# 5_power.net
KiCad netlist of a schematic drawn in Altium Designer
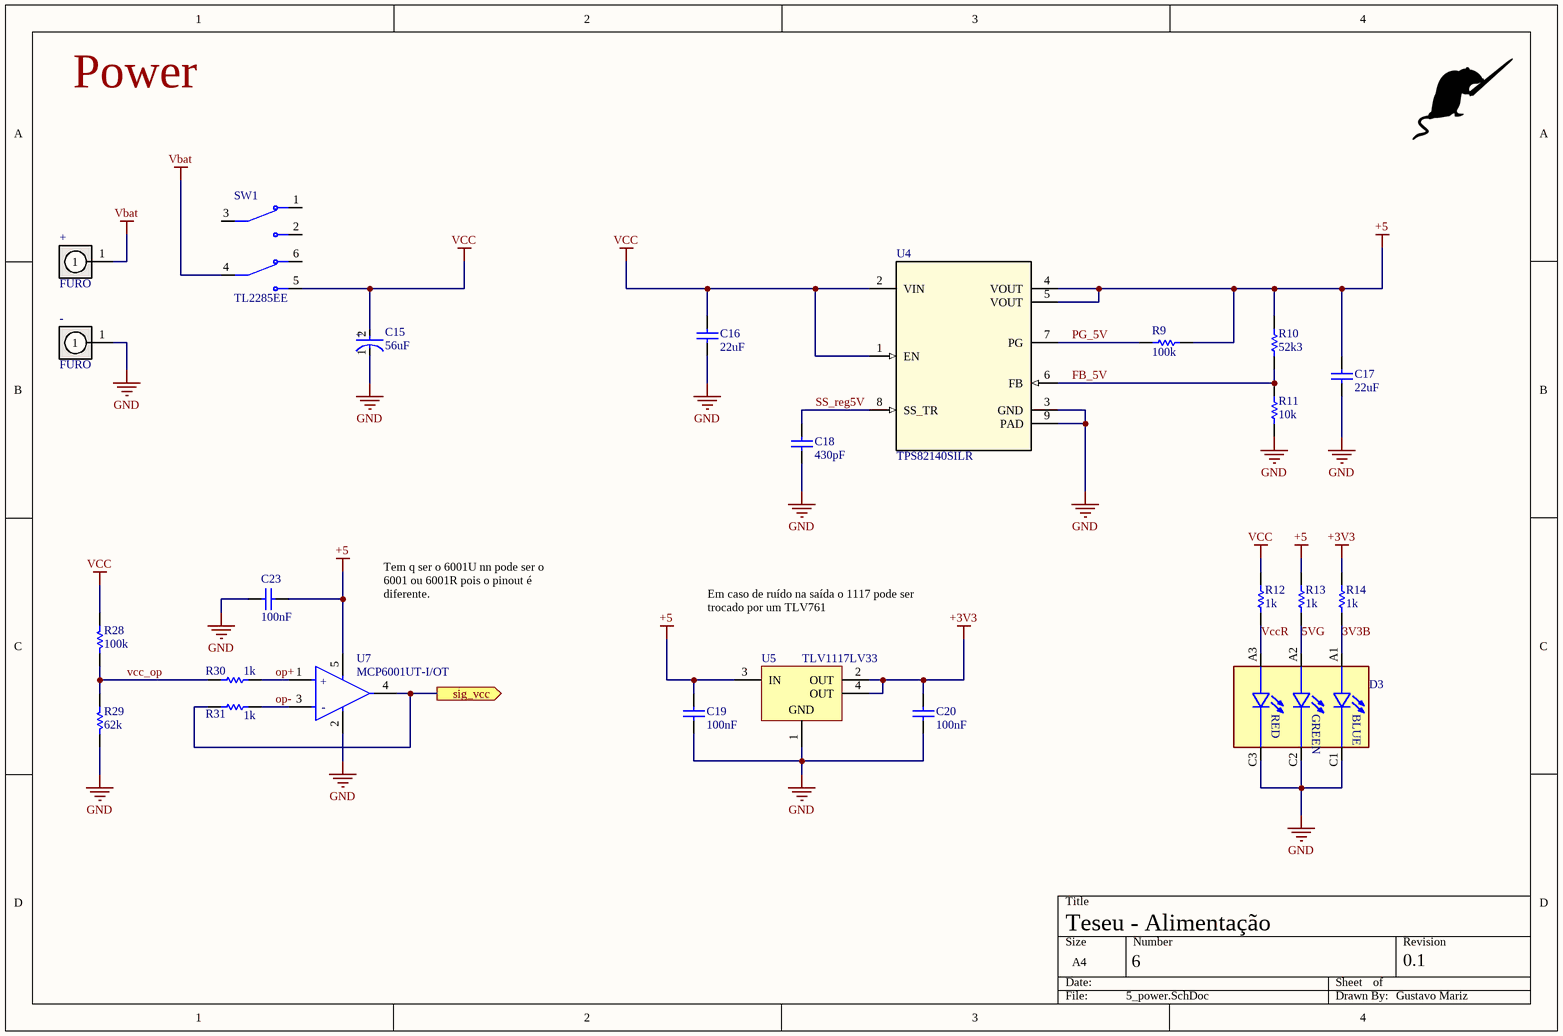
[diagram p0: 5_power.SchDoc]

(export (version "E")
  (design (tool "Eeschema 10.0.6"))
  (components
    (comp (ref "+")
      (value "FURO")
      (footprint "FURO_2,5MM")
      (description "Furo")
      (libsource (lib "Biblioteca Trincabotz (1)") (part "FURO NA PLACA"))
    )
    (comp (ref "-")
      (value "FURO")
      (footprint "FURO_2,5MM")
      (description "Furo")
      (libsource (lib "Biblioteca Trincabotz (1)") (part "FURO NA PLACA"))
    )
    (comp (ref "C15")
      (value "56uF")
      (footprint "FP-PSG-F05-MFG")
      (fields
        (field (name "OCTOPART") "https://octopart.com/apsg250ell560mf05s-united+chemi-con-70515924")
        (field (name "TOLERANCE") "20%")
        (field (name "MANUFACTURER") "United Chemi-Con")
      )
      (libsource (lib "Altium Content Vault") (part "a00bbbee19879c290e62620ae7e47b1"))
    )
    (comp (ref "C16")
      (value "CAP")
      (footprint "CAP 0805")
      (description "Capacitor")
      (fields (field (name "VALOR") "22uF"))
      (libsource (lib "Biblioteca Trincabotz (1)") (part "CAP. CERÂMICO"))
    )
    (comp (ref "C17")
      (value "CAP")
      (footprint "CAP 0805")
      (description "Capacitor")
      (fields (field (name "VALOR") "22uF"))
      (libsource (lib "Biblioteca Trincabotz (1)") (part "CAP. CERÂMICO"))
    )
    (comp (ref "C18")
      (value "CAP")
      (footprint "0603")
      (description "Capacitor")
      (fields (field (name "VALOR") "430pF"))
      (libsource (lib "Biblioteca Trincabotz (1)") (part "CAP. CERÂMICO"))
    )
    (comp (ref "C19")
      (value "CAP")
      (footprint "0603")
      (description "Capacitor")
      (fields (field (name "VALOR") "100nF"))
      (libsource (lib "Biblioteca Trincabotz (1)") (part "CAP. CERÂMICO"))
    )
    (comp (ref "C20")
      (value "CAP")
      (footprint "0603")
      (description "Capacitor")
      (fields (field (name "VALOR") "100nF"))
      (libsource (lib "Biblioteca Trincabotz (1)") (part "CAP. CERÂMICO"))
    )
    (comp (ref "C23")
      (value "CAP")
      (footprint "0603")
      (description "Capacitor")
      (fields (field (name "VALOR") "100nF"))
      (libsource (lib "Biblioteca Trincabotz (1)") (part "CAP. CERÂMICO"))
    )
    (comp (ref "D3")
      (value "KRTBLSLPS1.32-VUVX-EQ+BTBV-D8+TWTZ-L1-B")
      (footprint "LED_KRTBLSLPS1.32-VUVX-EQ+BTBV-D8+TWTZ-L1-B")
      (fields (field (name "MF") "OSRAM Opto Semiconductors Inc."))
      (libsource (lib "KRTBLSLPS1.32-VUVX-EQ_BTBV-D8_TWTZ-L1-B") (part "KRTBLSLPS1.32-VUVX-EQ+BTBV-D8+TWTZ-L1-B"))
    )
    (comp (ref "R9")
      (value "100k")
      (footprint "RES 0603")
      (description "Resistor")
      (fields (field (name "Comment") "RESISTOR"))
      (libsource (lib "Biblioteca Trincabotz (1)") (part "RESISTOR"))
    )
    (comp (ref "R10")
      (value "52k3")
      (footprint "RES 0603")
      (description "Resistor")
      (fields (field (name "Comment") "RESISTOR"))
      (libsource (lib "Biblioteca Trincabotz (1)") (part "RESISTOR"))
    )
    (comp (ref "R11")
      (value "10k")
      (footprint "RES 0603")
      (description "Resistor")
      (fields (field (name "Comment") "RESISTOR"))
      (libsource (lib "Biblioteca Trincabotz (1)") (part "RESISTOR"))
    )
    (comp (ref "R12")
      (value "1k")
      (footprint "RES 0603")
      (description "Resistor")
      (fields (field (name "Comment") "RESISTOR"))
      (libsource (lib "Biblioteca Trincabotz (1)") (part "RESISTOR"))
    )
    (comp (ref "R13")
      (value "1k")
      (footprint "RES 0603")
      (description "Resistor")
      (fields (field (name "Comment") "RESISTOR"))
      (libsource (lib "Biblioteca Trincabotz (1)") (part "RESISTOR"))
    )
    (comp (ref "R14")
      (value "1k")
      (footprint "RES 0603")
      (description "Resistor")
      (fields (field (name "Comment") "RESISTOR"))
      (libsource (lib "Biblioteca Trincabotz (1)") (part "RESISTOR"))
    )
    (comp (ref "R28")
      (value "100k")
      (footprint "RES 0603")
      (description "Resistor")
      (fields (field (name "Comment") "RESISTOR"))
      (libsource (lib "Biblioteca Trincabotz (1)") (part "RESISTOR"))
    )
    (comp (ref "R29")
      (value "62k")
      (footprint "RES 0603")
      (description "Resistor")
      (fields (field (name "Comment") "RESISTOR"))
      (libsource (lib "Biblioteca Trincabotz (1)") (part "RESISTOR"))
    )
    (comp (ref "R30")
      (value "1k")
      (footprint "RES 0603")
      (description "Resistor")
      (fields (field (name "Comment") "RESISTOR"))
      (libsource (lib "Biblioteca Trincabotz (1)") (part "RESISTOR"))
    )
    (comp (ref "R31")
      (value "1k")
      (footprint "RES 0603")
      (description "Resistor")
      (fields (field (name "Comment") "RESISTOR"))
      (libsource (lib "Biblioteca Trincabotz (1)") (part "RESISTOR"))
    )
    (comp (ref "SW1")
      (value "TL2285EE")
      (footprint "SW_TL2285EE")
      (libsource (lib "TL2285EE") (part "TL2285EE"))
    )
    (comp (ref "U4")
      (value "TPS82140SILR")
      (footprint "SIL0008D_SMD")
      (description "No Description Available")
      (libsource (lib "TPS82140SILR") (part "TPS82140SILR"))
    )
    (comp (ref "U5")
      (value "TLV1117LV33")
      (footprint "DCY0004A_N")
      (fields (field (name "MANUFACTURER") "Texas Instruments") (field (name "PARTNUMBER") "TLV1117LV33DCYR"))
      (libsource (lib "Altium Content Vault") (part "TI-TLV1117LV33DCY4"))
    )
    (comp (ref "U7")
      (value "MCP6001UT-I/OT")
      (footprint "FP-C04-091-OT-IPC_C")
      (description "IC OPAMP GP 1 CIRCUIT SOT23-5")
      (libsource (lib "Altium Content Vault") (part "dfdcf20f545b145ea91d4a0a3a74629"))
    )
  )
  (nets
    (net (code "1") (name "+3V3") (class "Default")
      (node (ref "C20") (pin "2") (pinfunction "2_2") (pintype "passive"))
      (node (ref "R14") (pin "2") (pinfunction "2_2") (pintype "passive"))
      (node (ref "U5") (pin "2") (pinfunction "OUT_2") (pintype "power_in"))
      (node (ref "U5") (pin "4") (pinfunction "OUT_4") (pintype "power_in"))
    )
    (net (code "2") (name "+5") (class "Default")
      (node (ref "C17") (pin "2") (pinfunction "2_2") (pintype "passive"))
      (node (ref "C19") (pin "2") (pinfunction "2_2") (pintype "passive"))
      (node (ref "C23") (pin "2") (pinfunction "2_2") (pintype "passive"))
      (node (ref "R10") (pin "2") (pinfunction "2_2") (pintype "passive"))
      (node (ref "R13") (pin "2") (pinfunction "2_2") (pintype "passive"))
      (node (ref "R9") (pin "1") (pinfunction "1_1") (pintype "passive"))
      (node (ref "U4") (pin "4") (pinfunction "VOUT_4") (pintype "power_in"))
      (node (ref "U4") (pin "5") (pinfunction "VOUT_5") (pintype "power_in"))
      (node (ref "U5") (pin "3") (pinfunction "IN_3") (pintype "power_in"))
      (node (ref "U7") (pin "5") (pinfunction "VDD_5") (pintype "power_in"))
    )
    (net (code "3") (name "/3V3B") (class "Default")
      (node (ref "D3") (pin "A1") (pinfunction "ANODE_BLUE_A1") (pintype "passive"))
      (node (ref "R14") (pin "1") (pinfunction "1_1") (pintype "passive"))
    )
    (net (code "4") (name "/5VG") (class "Default")
      (node (ref "D3") (pin "A2") (pinfunction "ANODE_TRUE_GREEN_A2") (pintype "passive"))
      (node (ref "R13") (pin "1") (pinfunction "1_1") (pintype "passive"))
    )
    (net (code "5") (name "/FB_5V") (class "Default")
      (node (ref "R10") (pin "1") (pinfunction "1_1") (pintype "passive"))
      (node (ref "R11") (pin "2") (pinfunction "2_2") (pintype "passive"))
      (node (ref "U4") (pin "6") (pinfunction "FB_6") (pintype "input"))
    )
    (net (code "6") (name "/PG_5V") (class "Default")
      (node (ref "R9") (pin "2") (pinfunction "2_2") (pintype "passive"))
      (node (ref "U4") (pin "7") (pinfunction "PG_7") (pintype "open_collector"))
    )
    (net (code "7") (name "/SS_reg5V") (class "Default")
      (node (ref "C18") (pin "2") (pinfunction "2_2") (pintype "passive"))
      (node (ref "U4") (pin "8") (pinfunction "SS_TR_8") (pintype "input"))
    )
    (net (code "8") (name "/VccR") (class "Default")
      (node (ref "D3") (pin "A3") (pinfunction "ANODE_RED_A3") (pintype "passive"))
      (node (ref "R12") (pin "1") (pinfunction "1_1") (pintype "passive"))
    )
    (net (code "9") (name "/op+") (class "Default")
      (node (ref "R30") (pin "2") (pinfunction "2_2") (pintype "passive"))
      (node (ref "U7") (pin "1") (pinfunction "VIN+_1") (pintype "tri_state"))
    )
    (net (code "10") (name "/op-") (class "Default")
      (node (ref "R31") (pin "2") (pinfunction "2_2") (pintype "passive"))
      (node (ref "U7") (pin "3") (pinfunction "VIN-_3") (pintype "tri_state"))
    )
    (net (code "11") (name "/sig_vcc") (class "Default")
      (node (ref "R31") (pin "1") (pinfunction "1_1") (pintype "passive"))
      (node (ref "U7") (pin "4") (pinfunction "VOUT_4") (pintype "passive"))
    )
    (net (code "12") (name "/vcc_op") (class "Default")
      (node (ref "R28") (pin "1") (pinfunction "1_1") (pintype "passive"))
      (node (ref "R29") (pin "2") (pinfunction "2_2") (pintype "passive"))
      (node (ref "R30") (pin "1") (pinfunction "1_1") (pintype "passive"))
    )
    (net (code "13") (name "GND") (class "Default")
      (node (ref "-") (pin "1") (pinfunction "1_1") (pintype "passive"))
      (node (ref "C15") (pin "1") (pinfunction "C_1") (pintype "passive"))
      (node (ref "C16") (pin "1") (pinfunction "1_1") (pintype "passive"))
      (node (ref "C17") (pin "1") (pinfunction "1_1") (pintype "passive"))
      (node (ref "C18") (pin "1") (pinfunction "1_1") (pintype "passive"))
      (node (ref "C19") (pin "1") (pinfunction "1_1") (pintype "passive"))
      (node (ref "C20") (pin "1") (pinfunction "1_1") (pintype "passive"))
      (node (ref "C23") (pin "1") (pinfunction "1_1") (pintype "passive"))
      (node (ref "D3") (pin "C1") (pinfunction "CATHODE_BLUE_C1") (pintype "passive"))
      (node (ref "D3") (pin "C2") (pinfunction "CATHODE_TRUE_GREEN_C2") (pintype "passive"))
      (node (ref "D3") (pin "C3") (pinfunction "CATHODE_RED_C3") (pintype "passive"))
      (node (ref "R11") (pin "1") (pinfunction "1_1") (pintype "passive"))
      (node (ref "R29") (pin "1") (pinfunction "1_1") (pintype "passive"))
      (node (ref "U4") (pin "3") (pinfunction "GND_3") (pintype "power_in"))
      (node (ref "U4") (pin "9") (pinfunction "PAD_9") (pintype "power_in"))
      (node (ref "U5") (pin "1") (pinfunction "GND_1") (pintype "power_in"))
      (node (ref "U7") (pin "2") (pinfunction "VSS_2") (pintype "power_in"))
    )
    (net (code "14") (name "VCC") (class "Default")
      (node (ref "C15") (pin "2") (pinfunction "A_2") (pintype "passive"))
      (node (ref "C16") (pin "2") (pinfunction "2_2") (pintype "passive"))
      (node (ref "R12") (pin "2") (pinfunction "2_2") (pintype "passive"))
      (node (ref "R28") (pin "2") (pinfunction "2_2") (pintype "passive"))
      (node (ref "SW1") (pin "5") (pinfunction "NO2_5") (pintype "passive"))
      (node (ref "U4") (pin "1") (pinfunction "EN_1") (pintype "input"))
      (node (ref "U4") (pin "2") (pinfunction "VIN_2") (pintype "power_in"))
    )
    (net (code "15") (name "Vbat") (class "Default")
      (node (ref "+") (pin "1") (pinfunction "1_1") (pintype "passive"))
      (node (ref "SW1") (pin "4") (pinfunction "COM2_4") (pintype "passive"))
    )
    (net (code "16") (name "unconnected-(SW1-COM1-Pad3)") (class "Default")
      (node (ref "SW1") (pin "3") (pinfunction "COM1_3") (pintype "passive"))
    )
    (net (code "17") (name "unconnected-(SW1-NC1-Pad1)") (class "Default")
      (node (ref "SW1") (pin "1") (pinfunction "NC1_1") (pintype "passive"))
    )
    (net (code "18") (name "unconnected-(SW1-NC2-Pad6)") (class "Default")
      (node (ref "SW1") (pin "6") (pinfunction "NC2_6") (pintype "passive"))
    )
    (net (code "19") (name "unconnected-(SW1-NO1-Pad2)") (class "Default")
      (node (ref "SW1") (pin "2") (pinfunction "NO1_2") (pintype "passive"))
    )
  )
)
